# Qwiic_MCP9600.net
KiCad netlist of a schematic drawn in EAGLE
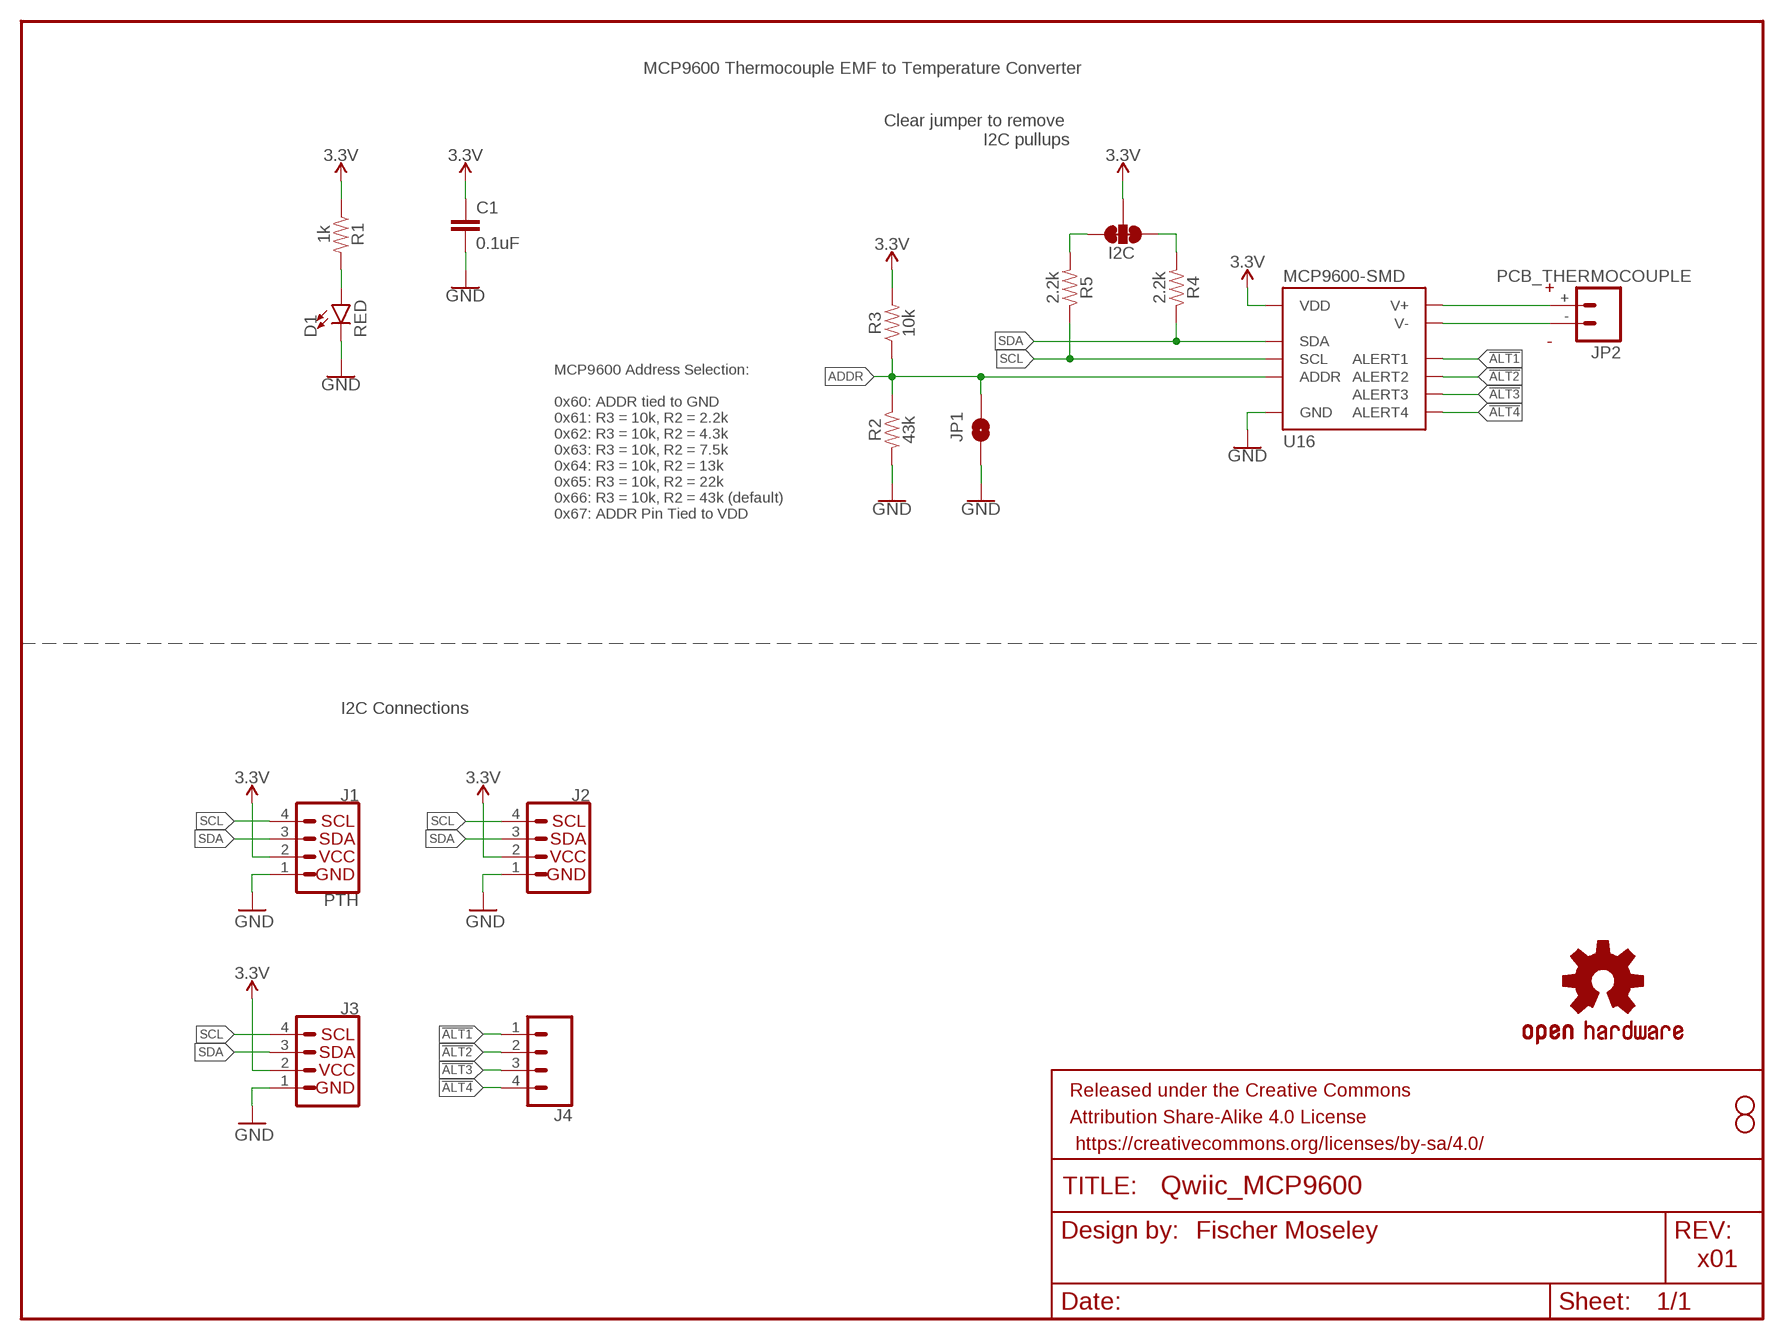
[diagram p0: schematic, sheet 1]

(export (version "E")
  (design (tool "Eeschema 10.0.6"))
  (components
    (comp (ref "C1")
      (value "0.1uF")
      (footprint "eagle-import:0603")
      (libsource (lib "eagle-import") (part "0.1UF-0603-25V-(+80/-20%)"))
    )
    (comp (ref "D1")
      (value "RED")
      (footprint "eagle-import:LED-0603")
      (libsource (lib "eagle-import") (part "LED-RED0603"))
    )
    (comp (ref "FRAME1")
      (value "FRAME-LETTER")
      (footprint "eagle-import:CREATIVE_COMMONS")
      (libsource (lib "eagle-import") (part "FRAME-LETTER"))
    )
    (comp (ref "I2C")
      (value "JUMPER-SMT_3_2-NC_TRACE_SILK")
      (footprint "eagle-import:SMT-JUMPER_3_2-NC_TRACE_SILK")
      (libsource (lib "eagle-import") (part "JUMPER-SMT_3_2-NC_TRACE_SILK"))
    )
    (comp (ref "J1")
      (value "PTH")
      (footprint "eagle-import:1X04_NO_SILK")
      (libsource (lib "eagle-import") (part "I2C_STANDARD_NO_SILK"))
    )
    (comp (ref "J2")
      (value "QWIIC_CONNECTORJS-1MM")
      (footprint "eagle-import:JST04_1MM_RA")
      (libsource (lib "eagle-import") (part "QWIIC_CONNECTORJS-1MM"))
    )
    (comp (ref "J3")
      (value "QWIIC_CONNECTORJS-1MM")
      (footprint "eagle-import:JST04_1MM_RA")
      (libsource (lib "eagle-import") (part "QWIIC_CONNECTORJS-1MM"))
    )
    (comp (ref "J4")
      (value "CONN_041X04_NO_SILK")
      (footprint "eagle-import:1X04_NO_SILK")
      (libsource (lib "eagle-import") (part "CONN_041X04_NO_SILK"))
    )
    (comp (ref "JP1")
      (value "JUMPER-SMT_2_NO_SILK")
      (footprint "eagle-import:SMT-JUMPER_2_NO_SILK")
      (libsource (lib "eagle-import") (part "JUMPER-SMT_2_NO_SILK"))
    )
    (comp (ref "JP2")
      (value "PCB_THERMOCOUPLE")
      (footprint "eagle-import:PCC-SMP")
      (libsource (lib "eagle-import") (part "PCB_THERMOCOUPLE"))
    )
    (comp (ref "JP8")
      (value "STAND-OFF")
      (footprint "eagle-import:STAND-OFF")
      (libsource (lib "eagle-import") (part "STAND-OFF"))
    )
    (comp (ref "JP9")
      (value "STAND-OFF")
      (footprint "eagle-import:STAND-OFF")
      (libsource (lib "eagle-import") (part "STAND-OFF"))
    )
    (comp (ref "LOGO1")
      (value "OSHW-LOGOMINI")
      (footprint "eagle-import:OSHW-LOGO-MINI")
      (libsource (lib "eagle-import") (part "OSHW-LOGOMINI"))
    )
    (comp (ref "R1")
      (value "1k")
      (footprint "eagle-import:0603")
      (libsource (lib "eagle-import") (part "1KOHM-0603-1/10W-1%"))
    )
    (comp (ref "R2")
      (value "43k")
      (footprint "eagle-import:0603")
      (libsource (lib "eagle-import") (part "43KOHM-0603-1/10W-1%"))
    )
    (comp (ref "R3")
      (value "10k")
      (footprint "eagle-import:0603")
      (libsource (lib "eagle-import") (part "10KOHM-0603-1/10W-1%"))
    )
    (comp (ref "R4")
      (value "2.2k")
      (footprint "eagle-import:0603")
      (libsource (lib "eagle-import") (part "2.2KOHM-0603-1/10W-1%"))
    )
    (comp (ref "R5")
      (value "2.2k")
      (footprint "eagle-import:0603")
      (libsource (lib "eagle-import") (part "2.2KOHM-0603-1/10W-1%"))
    )
    (comp (ref "U16")
      (value "MCP9600-SMD")
      (footprint "eagle-import:MQFN-20")
      (libsource (lib "eagle-import") (part "MCP9600-SMD"))
    )
  )
  (nets
    (net (code "1") (name "/~{ALT1}") (class "Default")
      (node (ref "J4") (pin "1") (pinfunction "1_1") (pintype "passive"))
      (node (ref "U16") (pin "11") (pinfunction "ALERT1_11") (pintype "bidirectional"))
    )
    (net (code "2") (name "/~{ALT2}") (class "Default")
      (node (ref "J4") (pin "2") (pinfunction "2_2") (pintype "passive"))
      (node (ref "U16") (pin "12") (pinfunction "ALERT2_12") (pintype "bidirectional"))
    )
    (net (code "3") (name "/~{ALT3}") (class "Default")
      (node (ref "J4") (pin "3") (pinfunction "3_3") (pintype "passive"))
      (node (ref "U16") (pin "14") (pinfunction "ALERT3_14") (pintype "bidirectional"))
    )
    (net (code "4") (name "/~{ALT4}") (class "Default")
      (node (ref "J4") (pin "4") (pinfunction "4_4") (pintype "passive"))
      (node (ref "U16") (pin "15") (pinfunction "ALERT4_15") (pintype "bidirectional"))
    )
    (net (code "5") (name "3.3V") (class "Default")
      (node (ref "C1") (pin "1") (pinfunction "1_1") (pintype "passive"))
      (node (ref "I2C") (pin "2") (pinfunction "2_2") (pintype "passive"))
      (node (ref "J1") (pin "2") (pinfunction "VCC_2") (pintype "power_in"))
      (node (ref "J2") (pin "2") (pinfunction "2_2") (pintype "power_in"))
      (node (ref "J3") (pin "2") (pinfunction "2_2") (pintype "power_in"))
      (node (ref "R1") (pin "1") (pinfunction "1_1") (pintype "passive"))
      (node (ref "R3") (pin "2") (pinfunction "2_2") (pintype "passive"))
      (node (ref "U16") (pin "8") (pinfunction "VDD_8") (pintype "bidirectional"))
    )
    (net (code "6") (name "ADDR") (class "Default")
      (node (ref "JP1") (pin "1") (pinfunction "1_1") (pintype "passive"))
      (node (ref "R2") (pin "1") (pinfunction "1_1") (pintype "passive"))
      (node (ref "R3") (pin "1") (pinfunction "1_1") (pintype "passive"))
      (node (ref "U16") (pin "16") (pinfunction "ADDR_16") (pintype "bidirectional"))
    )
    (net (code "7") (name "GND") (class "Default")
      (node (ref "C1") (pin "2") (pinfunction "2_2") (pintype "passive"))
      (node (ref "D1") (pin "C") (pinfunction "C_C") (pintype "passive"))
      (node (ref "J1") (pin "1") (pinfunction "GND_1") (pintype "power_in"))
      (node (ref "J2") (pin "1") (pinfunction "1_1") (pintype "power_in"))
      (node (ref "J3") (pin "1") (pinfunction "1_1") (pintype "power_in"))
      (node (ref "JP1") (pin "2") (pinfunction "2_2") (pintype "passive"))
      (node (ref "R2") (pin "2") (pinfunction "2_2") (pintype "passive"))
      (node (ref "U16") (pin "1") (pinfunction "GND_1") (pintype "bidirectional"))
      (node (ref "U16") (pin "10") (pinfunction "GND_10") (pintype "bidirectional"))
      (node (ref "U16") (pin "13") (pinfunction "GND_13") (pintype "bidirectional"))
      (node (ref "U16") (pin "17") (pinfunction "GND_17") (pintype "bidirectional"))
      (node (ref "U16") (pin "18") (pinfunction "GND_18") (pintype "bidirectional"))
      (node (ref "U16") (pin "21") (pinfunction "GND_21") (pintype "bidirectional"))
      (node (ref "U16") (pin "3") (pinfunction "GND_3") (pintype "bidirectional"))
      (node (ref "U16") (pin "5") (pinfunction "GND_5") (pintype "bidirectional"))
      (node (ref "U16") (pin "6") (pinfunction "GND_6") (pintype "bidirectional"))
      (node (ref "U16") (pin "7") (pinfunction "GND_7") (pintype "bidirectional"))
      (node (ref "U16") (pin "9") (pinfunction "GND_9") (pintype "bidirectional"))
    )
    (net (code "8") (name "Net-(D1-PadA)") (class "Default")
      (node (ref "D1") (pin "A") (pinfunction "A_A") (pintype "passive"))
      (node (ref "R1") (pin "2") (pinfunction "2_2") (pintype "passive"))
    )
    (net (code "9") (name "Net-(I2C-Pad1)") (class "Default")
      (node (ref "I2C") (pin "1") (pinfunction "1_1") (pintype "passive"))
      (node (ref "R5") (pin "2") (pinfunction "2_2") (pintype "passive"))
    )
    (net (code "10") (name "Net-(I2C-Pad3)") (class "Default")
      (node (ref "I2C") (pin "3") (pinfunction "3_3") (pintype "passive"))
      (node (ref "R4") (pin "2") (pinfunction "2_2") (pintype "passive"))
    )
    (net (code "11") (name "Net-(U16-V+)") (class "Default")
      (node (ref "JP2") (pin "+") (pinfunction "+_+") (pintype "passive"))
      (node (ref "U16") (pin "2") (pinfunction "V+_2") (pintype "bidirectional"))
    )
    (net (code "12") (name "Net-(U16-V-)") (class "Default")
      (node (ref "JP2") (pin "-") (pinfunction "-_-") (pintype "passive"))
      (node (ref "U16") (pin "4") (pinfunction "V-_4") (pintype "bidirectional"))
    )
    (net (code "13") (name "SCL") (class "Default")
      (node (ref "J1") (pin "4") (pinfunction "SCL_4") (pintype "passive"))
      (node (ref "J2") (pin "4") (pinfunction "4_4") (pintype "passive"))
      (node (ref "J3") (pin "4") (pinfunction "4_4") (pintype "passive"))
      (node (ref "R5") (pin "1") (pinfunction "1_1") (pintype "passive"))
      (node (ref "U16") (pin "19") (pinfunction "SCL_19") (pintype "bidirectional"))
    )
    (net (code "14") (name "SDA") (class "Default")
      (node (ref "J1") (pin "3") (pinfunction "SDA_3") (pintype "passive"))
      (node (ref "J2") (pin "3") (pinfunction "3_3") (pintype "passive"))
      (node (ref "J3") (pin "3") (pinfunction "3_3") (pintype "passive"))
      (node (ref "R4") (pin "1") (pinfunction "1_1") (pintype "passive"))
      (node (ref "U16") (pin "20") (pinfunction "SDA_20") (pintype "bidirectional"))
    )
  )
)
